# Touch_Shield.net
KiCad netlist of a schematic drawn in EAGLE
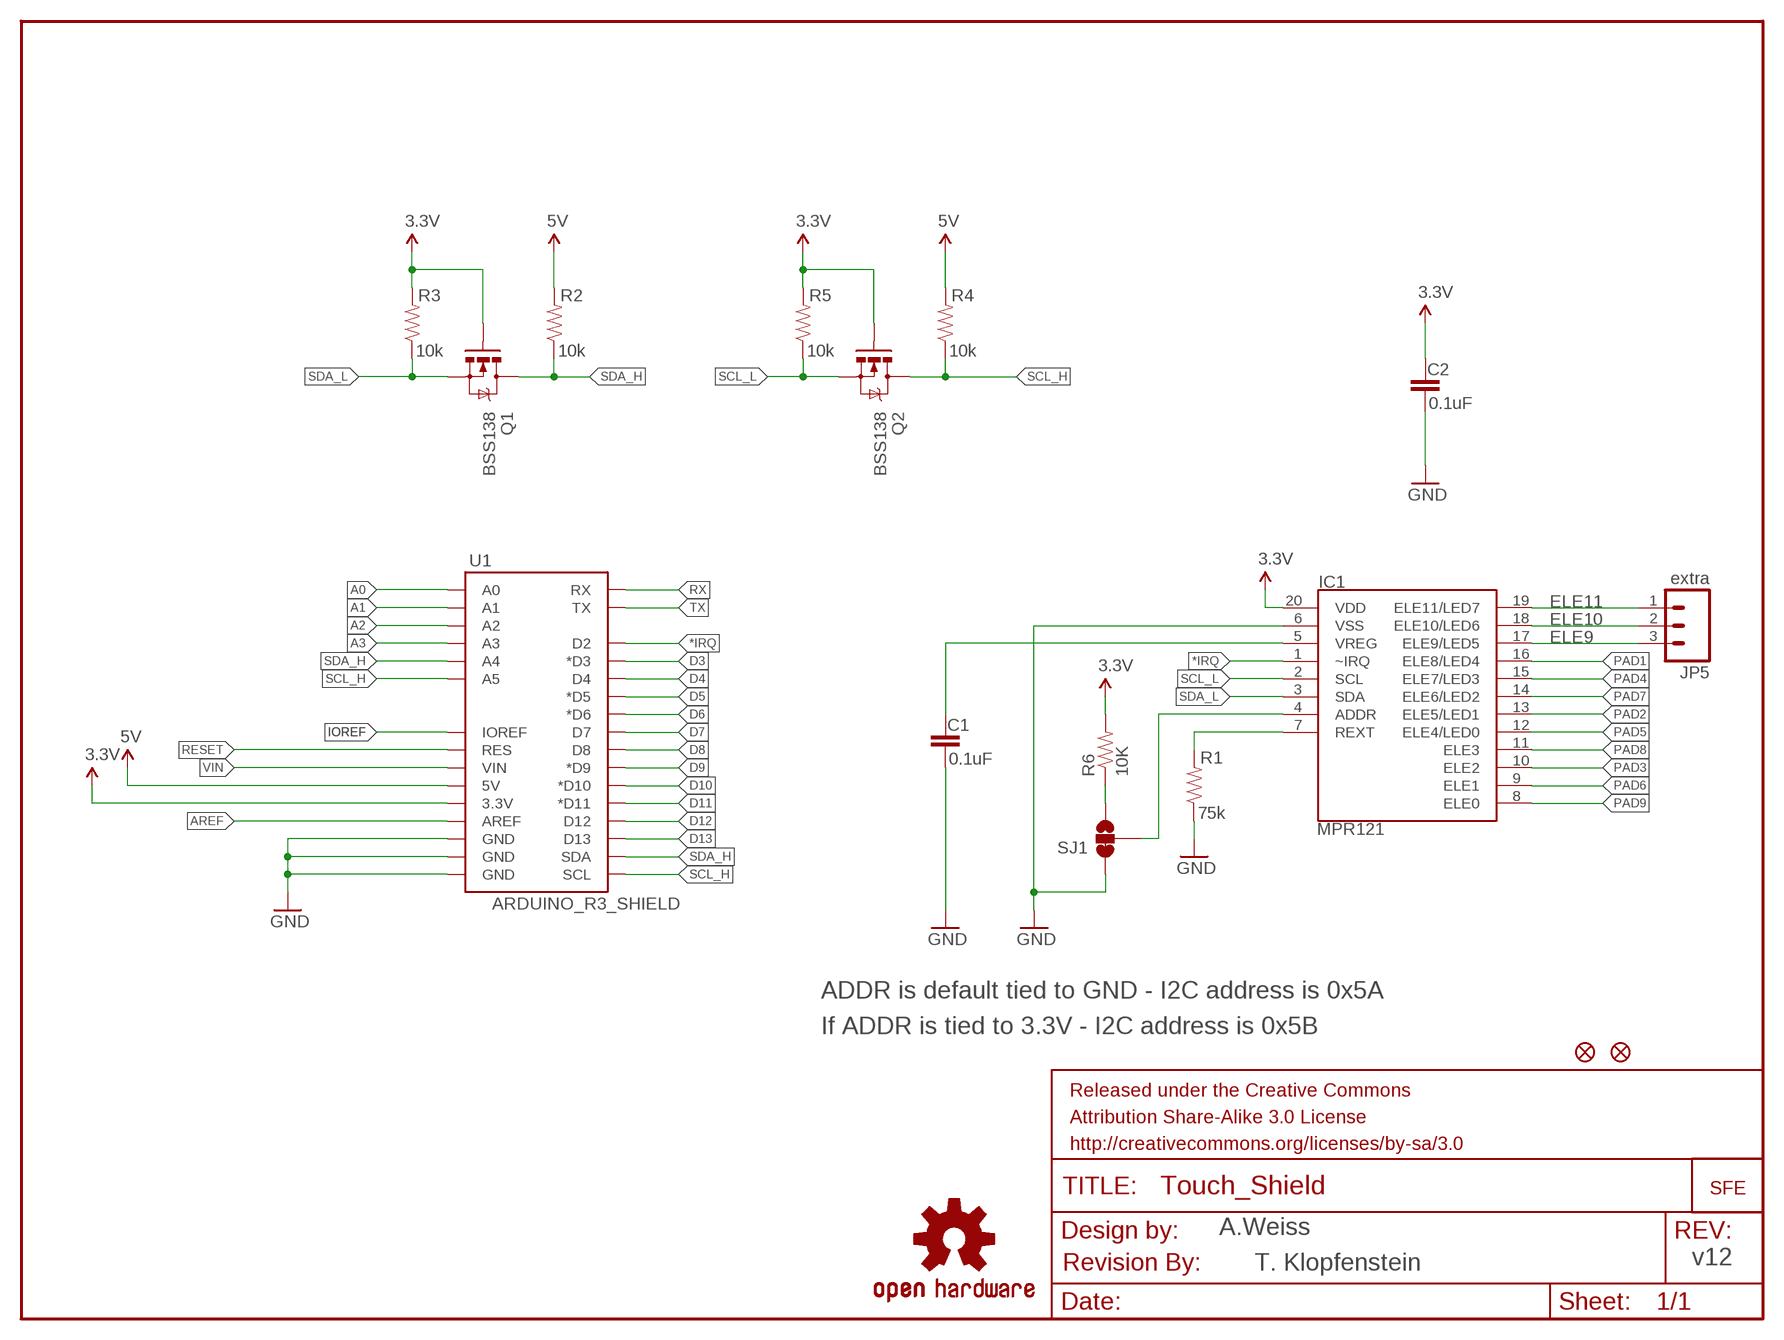
[diagram p0: schematic, sheet 1]

(export (version "E")
  (design (tool "Eeschema 10.0.6"))
  (components
    (comp (ref "C1")
      (value "0.1uF")
      (footprint "eagle-import:0603-CAP")
      (libsource (lib "eagle-import") (part "CAP0603-CAP"))
    )
    (comp (ref "C2")
      (value "0.1uF")
      (footprint "eagle-import:0603-CAP")
      (libsource (lib "eagle-import") (part "CAP0603-CAP"))
    )
    (comp (ref "FID1")
      (value "FIDUCIALUFIDUCIAL")
      (footprint "eagle-import:MICRO-FIDUCIAL")
      (libsource (lib "eagle-import") (part "FIDUCIALUFIDUCIAL"))
    )
    (comp (ref "FID2")
      (value "FIDUCIALUFIDUCIAL")
      (footprint "eagle-import:MICRO-FIDUCIAL")
      (libsource (lib "eagle-import") (part "FIDUCIALUFIDUCIAL"))
    )
    (comp (ref "FRAME1")
      (value "FRAME-LETTER")
      (footprint "eagle-import:CREATIVE_COMMONS")
      (libsource (lib "eagle-import") (part "FRAME-LETTER"))
    )
    (comp (ref "IC1")
      (value "MPR121")
      (footprint "eagle-import:QFN-20-0.4MM-V2")
      (libsource (lib "eagle-import") (part "MPR121V2"))
    )
    (comp (ref "JP1")
      (value "LOGO-SFENEW")
      (footprint "eagle-import:SFE-NEW-WEBLOGO")
      (libsource (lib "eagle-import") (part "LOGO-SFENEW"))
    )
    (comp (ref "JP5")
      (value "extra")
      (footprint "eagle-import:1X03")
      (libsource (lib "eagle-import") (part "M03PTH"))
    )
    (comp (ref "Q1")
      (value "BSS138")
      (footprint "eagle-import:SOT23-3")
      (libsource (lib "eagle-import") (part "MOSFET-NCHANNELSMD"))
    )
    (comp (ref "Q2")
      (value "BSS138")
      (footprint "eagle-import:SOT23-3")
      (libsource (lib "eagle-import") (part "MOSFET-NCHANNELSMD"))
    )
    (comp (ref "R1")
      (value "75k")
      (footprint "eagle-import:0603-RES")
      (libsource (lib "eagle-import") (part "RESISTOR0603-RES"))
    )
    (comp (ref "R2")
      (value "10k")
      (footprint "eagle-import:0603-RES")
      (libsource (lib "eagle-import") (part "10KOHM1/10W1%(0603)0603"))
    )
    (comp (ref "R3")
      (value "10k")
      (footprint "eagle-import:0603-RES")
      (libsource (lib "eagle-import") (part "10KOHM1/10W1%(0603)0603"))
    )
    (comp (ref "R4")
      (value "10k")
      (footprint "eagle-import:0603-RES")
      (libsource (lib "eagle-import") (part "10KOHM1/10W1%(0603)0603"))
    )
    (comp (ref "R5")
      (value "10k")
      (footprint "eagle-import:0603-RES")
      (libsource (lib "eagle-import") (part "10KOHM1/10W1%(0603)0603"))
    )
    (comp (ref "R6")
      (value "10K")
      (footprint "eagle-import:0603-RES")
      (libsource (lib "eagle-import") (part "10KOHM1/10W1%(0603)0603"))
    )
    (comp (ref "SJ1")
      (value "SOLDERJUMPER_2WAYPASTE1&2")
      (footprint "eagle-import:SJ_3_PASTE1&2")
      (libsource (lib "eagle-import") (part "SOLDERJUMPER_2WAYPASTE1&2"))
    )
    (comp (ref "U$1")
      (value "REVISION")
      (footprint "eagle-import:REVISION")
      (libsource (lib "eagle-import") (part "REVISION"))
    )
    (comp (ref "U$5")
      (value "OSHW-LOGOL")
      (footprint "eagle-import:OSHW-LOGO-L")
      (libsource (lib "eagle-import") (part "OSHW-LOGOL"))
    )
    (comp (ref "U1")
      (value "ARDUINO_R3_SHIELD")
      (footprint "eagle-import:UNO_R3_SHIELD")
      (libsource (lib "eagle-import") (part "ARDUINO_R3_SHIELD"))
    )
  )
  (nets
    (net (code "1") (name "*IRQ") (class "Default")
      (node (ref "IC1") (pin "1") (pinfunction "~{IRQ}_1") (pintype "bidirectional"))
      (node (ref "U1") (pin "D2") (pinfunction "D2_D2") (pintype "bidirectional"))
    )
    (net (code "2") (name "/ELE9") (class "Default")
      (node (ref "IC1") (pin "17") (pinfunction "ELE9/LED5_17") (pintype "bidirectional"))
      (node (ref "JP5") (pin "3") (pinfunction "3_3") (pintype "passive"))
    )
    (net (code "3") (name "/ELE10") (class "Default")
      (node (ref "IC1") (pin "18") (pinfunction "ELE10/LED6_18") (pintype "bidirectional"))
      (node (ref "JP5") (pin "2") (pinfunction "2_2") (pintype "passive"))
    )
    (net (code "4") (name "/ELE11") (class "Default")
      (node (ref "IC1") (pin "19") (pinfunction "ELE11/LED7_19") (pintype "bidirectional"))
      (node (ref "JP5") (pin "1") (pinfunction "1_1") (pintype "passive"))
    )
    (net (code "5") (name "3.3V") (class "Default")
      (node (ref "C2") (pin "1") (pinfunction "1_1") (pintype "passive"))
      (node (ref "IC1") (pin "20") (pinfunction "VDD_20") (pintype "bidirectional"))
      (node (ref "Q1") (pin "1") (pinfunction "G_1") (pintype "passive"))
      (node (ref "Q2") (pin "1") (pinfunction "G_1") (pintype "passive"))
      (node (ref "R3") (pin "2") (pinfunction "2_2") (pintype "passive"))
      (node (ref "R5") (pin "2") (pinfunction "2_2") (pintype "passive"))
      (node (ref "R6") (pin "2") (pinfunction "2_2") (pintype "passive"))
      (node (ref "U1") (pin "3.3V") (pinfunction "3.3V_3.3V") (pintype "bidirectional"))
    )
    (net (code "6") (name "5V") (class "Default")
      (node (ref "R2") (pin "2") (pinfunction "2_2") (pintype "passive"))
      (node (ref "R4") (pin "2") (pinfunction "2_2") (pintype "passive"))
      (node (ref "U1") (pin "5V") (pinfunction "5V_5V") (pintype "bidirectional"))
    )
    (net (code "7") (name "A0") (class "Default")
      (node (ref "U1") (pin "A0") (pinfunction "A0_A0") (pintype "bidirectional"))
    )
    (net (code "8") (name "A1") (class "Default")
      (node (ref "U1") (pin "A1") (pinfunction "A1_A1") (pintype "bidirectional"))
    )
    (net (code "9") (name "A2") (class "Default")
      (node (ref "U1") (pin "A2") (pinfunction "A2_A2") (pintype "bidirectional"))
    )
    (net (code "10") (name "A3") (class "Default")
      (node (ref "U1") (pin "A3") (pinfunction "A3_A3") (pintype "bidirectional"))
    )
    (net (code "11") (name "AREF") (class "Default")
      (node (ref "U1") (pin "AREF") (pinfunction "AREF_AREF") (pintype "bidirectional"))
    )
    (net (code "12") (name "D3") (class "Default")
      (node (ref "U1") (pin "D3") (pinfunction "*D3_D3") (pintype "bidirectional"))
    )
    (net (code "13") (name "D4") (class "Default")
      (node (ref "U1") (pin "D4") (pinfunction "D4_D4") (pintype "bidirectional"))
    )
    (net (code "14") (name "D5") (class "Default")
      (node (ref "U1") (pin "D5") (pinfunction "*D5_D5") (pintype "bidirectional"))
    )
    (net (code "15") (name "D6") (class "Default")
      (node (ref "U1") (pin "D6") (pinfunction "*D6_D6") (pintype "bidirectional"))
    )
    (net (code "16") (name "D7") (class "Default")
      (node (ref "U1") (pin "D7") (pinfunction "D7_D7") (pintype "bidirectional"))
    )
    (net (code "17") (name "D8") (class "Default")
      (node (ref "U1") (pin "D8") (pinfunction "D8_D8") (pintype "bidirectional"))
    )
    (net (code "18") (name "D9") (class "Default")
      (node (ref "U1") (pin "D9") (pinfunction "*D9_D9") (pintype "bidirectional"))
    )
    (net (code "19") (name "D10") (class "Default")
      (node (ref "U1") (pin "D10") (pinfunction "*D10_D10") (pintype "bidirectional"))
    )
    (net (code "20") (name "D11") (class "Default")
      (node (ref "U1") (pin "D11") (pinfunction "*D11_D11") (pintype "bidirectional"))
    )
    (net (code "21") (name "D12") (class "Default")
      (node (ref "U1") (pin "D12") (pinfunction "D12_D12") (pintype "bidirectional"))
    )
    (net (code "22") (name "D13") (class "Default")
      (node (ref "U1") (pin "D13") (pinfunction "D13_D13") (pintype "bidirectional"))
    )
    (net (code "23") (name "GND") (class "Default")
      (node (ref "C1") (pin "2") (pinfunction "2_2") (pintype "passive"))
      (node (ref "C2") (pin "2") (pinfunction "2_2") (pintype "passive"))
      (node (ref "IC1") (pin "6") (pinfunction "VSS_6") (pintype "bidirectional"))
      (node (ref "R1") (pin "1") (pinfunction "1_1") (pintype "passive"))
      (node (ref "SJ1") (pin "1") (pinfunction "1_1") (pintype "passive"))
      (node (ref "U1") (pin "GND@0") (pinfunction "GND_GND@0") (pintype "bidirectional"))
      (node (ref "U1") (pin "GND@1") (pinfunction "GND_GND@1") (pintype "bidirectional"))
      (node (ref "U1") (pin "GND@2") (pinfunction "GND_GND@2") (pintype "bidirectional"))
    )
    (net (code "24") (name "IOREF") (class "Default")
      (node (ref "U1") (pin "IOREF") (pinfunction "IOREF_IOREF") (pintype "bidirectional"))
    )
    (net (code "25") (name "Net-(IC1-ADDR)") (class "Default")
      (node (ref "IC1") (pin "4") (pinfunction "ADDR_4") (pintype "bidirectional"))
      (node (ref "SJ1") (pin "2") (pinfunction "2_2") (pintype "passive"))
    )
    (net (code "26") (name "Net-(IC1-REXT)") (class "Default")
      (node (ref "IC1") (pin "7") (pinfunction "REXT_7") (pintype "bidirectional"))
      (node (ref "R1") (pin "2") (pinfunction "2_2") (pintype "passive"))
    )
    (net (code "27") (name "Net-(IC1-VREG)") (class "Default")
      (node (ref "C1") (pin "1") (pinfunction "1_1") (pintype "passive"))
      (node (ref "IC1") (pin "5") (pinfunction "VREG_5") (pintype "bidirectional"))
    )
    (net (code "28") (name "Net-(R6-Pad1)") (class "Default")
      (node (ref "R6") (pin "1") (pinfunction "1_1") (pintype "passive"))
      (node (ref "SJ1") (pin "3") (pinfunction "3_3") (pintype "passive"))
    )
    (net (code "29") (name "PAD1") (class "Default")
      (node (ref "IC1") (pin "16") (pinfunction "ELE8/LED4_16") (pintype "bidirectional"))
    )
    (net (code "30") (name "PAD2") (class "Default")
      (node (ref "IC1") (pin "13") (pinfunction "ELE5/LED1_13") (pintype "bidirectional"))
    )
    (net (code "31") (name "PAD3") (class "Default")
      (node (ref "IC1") (pin "10") (pinfunction "ELE2_10") (pintype "bidirectional"))
    )
    (net (code "32") (name "PAD4") (class "Default")
      (node (ref "IC1") (pin "15") (pinfunction "ELE7/LED3_15") (pintype "bidirectional"))
    )
    (net (code "33") (name "PAD5") (class "Default")
      (node (ref "IC1") (pin "12") (pinfunction "ELE4/LED0_12") (pintype "bidirectional"))
    )
    (net (code "34") (name "PAD6") (class "Default")
      (node (ref "IC1") (pin "9") (pinfunction "ELE1_9") (pintype "bidirectional"))
    )
    (net (code "35") (name "PAD7") (class "Default")
      (node (ref "IC1") (pin "14") (pinfunction "ELE6/LED2_14") (pintype "bidirectional"))
    )
    (net (code "36") (name "PAD8") (class "Default")
      (node (ref "IC1") (pin "11") (pinfunction "ELE3_11") (pintype "bidirectional"))
    )
    (net (code "37") (name "PAD9") (class "Default")
      (node (ref "IC1") (pin "8") (pinfunction "ELE0_8") (pintype "bidirectional"))
    )
    (net (code "38") (name "RESET") (class "Default")
      (node (ref "U1") (pin "RES") (pinfunction "RES_RES") (pintype "bidirectional"))
    )
    (net (code "39") (name "RX") (class "Default")
      (node (ref "U1") (pin "RX") (pinfunction "RX_RX") (pintype "bidirectional"))
    )
    (net (code "40") (name "SCL_H") (class "Default")
      (node (ref "Q2") (pin "3") (pinfunction "D_3") (pintype "passive"))
      (node (ref "R4") (pin "1") (pinfunction "1_1") (pintype "passive"))
      (node (ref "U1") (pin "A5") (pinfunction "A5_A5") (pintype "bidirectional"))
      (node (ref "U1") (pin "SCL") (pinfunction "SCL_SCL") (pintype "bidirectional"))
    )
    (net (code "41") (name "SCL_L") (class "Default")
      (node (ref "IC1") (pin "2") (pinfunction "SCL_2") (pintype "bidirectional"))
      (node (ref "Q2") (pin "2") (pinfunction "S_2") (pintype "passive"))
      (node (ref "R5") (pin "1") (pinfunction "1_1") (pintype "passive"))
    )
    (net (code "42") (name "SDA_H") (class "Default")
      (node (ref "Q1") (pin "3") (pinfunction "D_3") (pintype "passive"))
      (node (ref "R2") (pin "1") (pinfunction "1_1") (pintype "passive"))
      (node (ref "U1") (pin "A4") (pinfunction "A4_A4") (pintype "bidirectional"))
      (node (ref "U1") (pin "SDA") (pinfunction "SDA_SDA") (pintype "bidirectional"))
    )
    (net (code "43") (name "SDA_L") (class "Default")
      (node (ref "IC1") (pin "3") (pinfunction "SDA_3") (pintype "bidirectional"))
      (node (ref "Q1") (pin "2") (pinfunction "S_2") (pintype "passive"))
      (node (ref "R3") (pin "1") (pinfunction "1_1") (pintype "passive"))
    )
    (net (code "44") (name "TX") (class "Default")
      (node (ref "U1") (pin "TX") (pinfunction "TX_TX") (pintype "bidirectional"))
    )
    (net (code "45") (name "VIN") (class "Default")
      (node (ref "U1") (pin "VIN") (pinfunction "VIN_VIN") (pintype "bidirectional"))
    )
  )
)
